# Adafruit_NeoPixel_Ring_60_Quarter_rev_B.net
KiCad netlist of a schematic drawn in EAGLE
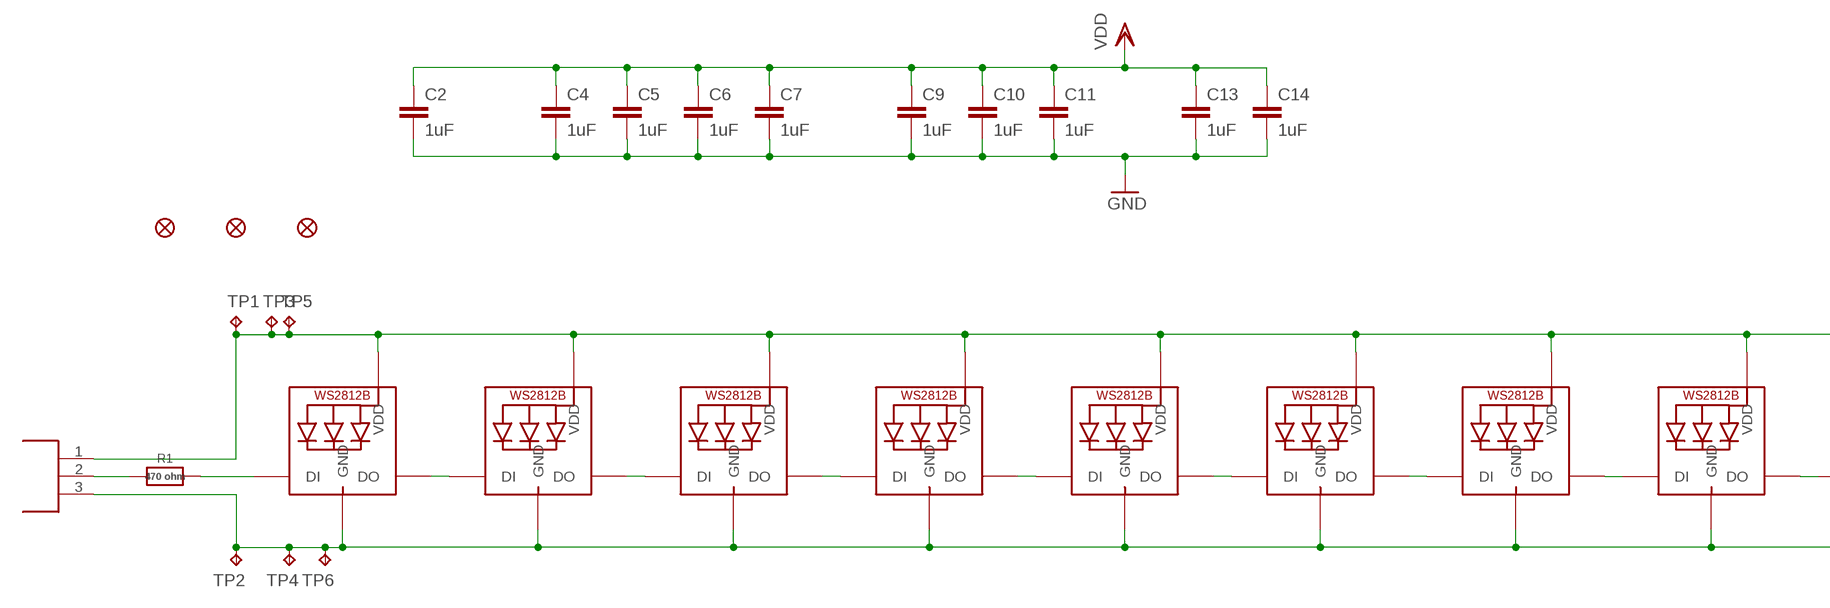
[diagram p0: schematic, sheet 1, part 1 of 2]
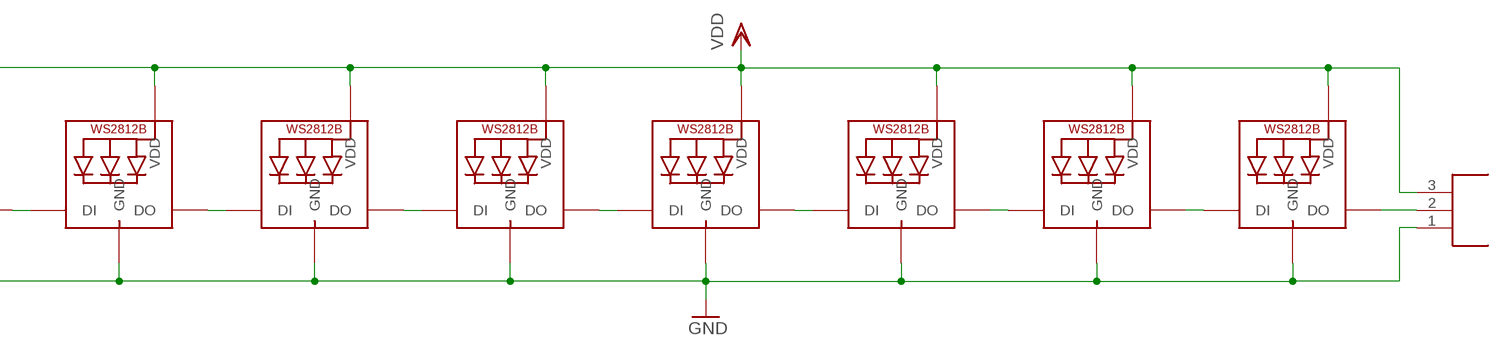
[diagram p1: schematic, sheet 1, part 2 of 2]

(export (version "E")
  (design (tool "Eeschema 10.0.6"))
  (components
    (comp (ref "C2")
      (value "1uF")
      (footprint "eagle-import:C0603")
      (libsource (lib "eagle-import") (part "C-EUC0603"))
    )
    (comp (ref "C4")
      (value "1uF")
      (footprint "eagle-import:C0603")
      (libsource (lib "eagle-import") (part "C-EUC0603"))
    )
    (comp (ref "C5")
      (value "1uF")
      (footprint "eagle-import:C0603")
      (libsource (lib "eagle-import") (part "C-EUC0603"))
    )
    (comp (ref "C6")
      (value "1uF")
      (footprint "eagle-import:C0603")
      (libsource (lib "eagle-import") (part "C-EUC0603"))
    )
    (comp (ref "C7")
      (value "1uF")
      (footprint "eagle-import:C0603")
      (libsource (lib "eagle-import") (part "C-EUC0603"))
    )
    (comp (ref "C9")
      (value "1uF")
      (footprint "eagle-import:C0603")
      (libsource (lib "eagle-import") (part "C-EUC0603"))
    )
    (comp (ref "C10")
      (value "1uF")
      (footprint "eagle-import:C0603")
      (libsource (lib "eagle-import") (part "C-EUC0603"))
    )
    (comp (ref "C11")
      (value "1uF")
      (footprint "eagle-import:C0603")
      (libsource (lib "eagle-import") (part "C-EUC0603"))
    )
    (comp (ref "C13")
      (value "1uF")
      (footprint "eagle-import:C0603")
      (libsource (lib "eagle-import") (part "C-EUC0603"))
    )
    (comp (ref "C14")
      (value "1uF")
      (footprint "eagle-import:C0603")
      (libsource (lib "eagle-import") (part "C-EUC0603"))
    )
    (comp (ref "FID1")
      (value "FIDUCIAL_1MM")
      (footprint "eagle-import:FIDUCIAL_1MM")
      (libsource (lib "eagle-import") (part "FIDUCIAL_1MM"))
    )
    (comp (ref "FID2")
      (value "FIDUCIAL_1MM")
      (footprint "eagle-import:FIDUCIAL_1MM")
      (libsource (lib "eagle-import") (part "FIDUCIAL_1MM"))
    )
    (comp (ref "FID3")
      (value "FIDUCIAL_1MM")
      (footprint "eagle-import:FIDUCIAL_1MM")
      (libsource (lib "eagle-import") (part "FIDUCIAL_1MM"))
    )
    (comp (ref "LED1")
      (value "WS2812B_5050N")
      (footprint "eagle-import:WS2812B-NARROW")
      (libsource (lib "eagle-import") (part "WS2812B_5050N"))
    )
    (comp (ref "LED2")
      (value "WS2812B_5050N")
      (footprint "eagle-import:WS2812B-NARROW")
      (libsource (lib "eagle-import") (part "WS2812B_5050N"))
    )
    (comp (ref "LED3")
      (value "WS2812B_5050N")
      (footprint "eagle-import:WS2812B-NARROW")
      (libsource (lib "eagle-import") (part "WS2812B_5050N"))
    )
    (comp (ref "LED4")
      (value "WS2812B_5050N")
      (footprint "eagle-import:WS2812B-NARROW")
      (libsource (lib "eagle-import") (part "WS2812B_5050N"))
    )
    (comp (ref "LED5")
      (value "WS2812B_5050N")
      (footprint "eagle-import:WS2812B-NARROW")
      (libsource (lib "eagle-import") (part "WS2812B_5050N"))
    )
    (comp (ref "LED6")
      (value "WS2812B_5050N")
      (footprint "eagle-import:WS2812B-NARROW")
      (libsource (lib "eagle-import") (part "WS2812B_5050N"))
    )
    (comp (ref "LED7")
      (value "WS2812B_5050N")
      (footprint "eagle-import:WS2812B-NARROW")
      (libsource (lib "eagle-import") (part "WS2812B_5050N"))
    )
    (comp (ref "LED8")
      (value "WS2812B_5050N")
      (footprint "eagle-import:WS2812B-NARROW")
      (libsource (lib "eagle-import") (part "WS2812B_5050N"))
    )
    (comp (ref "LED9")
      (value "WS2812B_5050N")
      (footprint "eagle-import:WS2812B-NARROW")
      (libsource (lib "eagle-import") (part "WS2812B_5050N"))
    )
    (comp (ref "LED10")
      (value "WS2812B_5050N")
      (footprint "eagle-import:WS2812B-NARROW")
      (libsource (lib "eagle-import") (part "WS2812B_5050N"))
    )
    (comp (ref "LED11")
      (value "WS2812B_5050N")
      (footprint "eagle-import:WS2812B-NARROW")
      (libsource (lib "eagle-import") (part "WS2812B_5050N"))
    )
    (comp (ref "LED12")
      (value "WS2812B_5050N")
      (footprint "eagle-import:WS2812B-NARROW")
      (libsource (lib "eagle-import") (part "WS2812B_5050N"))
    )
    (comp (ref "LED13")
      (value "WS2812B_5050N")
      (footprint "eagle-import:WS2812B-NARROW")
      (libsource (lib "eagle-import") (part "WS2812B_5050N"))
    )
    (comp (ref "LED14")
      (value "WS2812B_5050N")
      (footprint "eagle-import:WS2812B-NARROW")
      (libsource (lib "eagle-import") (part "WS2812B_5050N"))
    )
    (comp (ref "LED15")
      (value "WS2812B_5050N")
      (footprint "eagle-import:WS2812B-NARROW")
      (libsource (lib "eagle-import") (part "WS2812B_5050N"))
    )
    (comp (ref "R1")
      (value "470 ohm")
      (footprint "eagle-import:0603-NO")
      (libsource (lib "eagle-import") (part "RESISTOR_0603_NOOUT"))
    )
    (comp (ref "TP1")
      (value "TPTP20R")
      (footprint "eagle-import:TP20R")
      (libsource (lib "eagle-import") (part "TPTP20R"))
    )
    (comp (ref "TP2")
      (value "TPTP20R")
      (footprint "eagle-import:TP20R")
      (libsource (lib "eagle-import") (part "TPTP20R"))
    )
    (comp (ref "TP3")
      (value "TPTP20R")
      (footprint "eagle-import:TP20R")
      (libsource (lib "eagle-import") (part "TPTP20R"))
    )
    (comp (ref "TP4")
      (value "TPTP20R")
      (footprint "eagle-import:TP20R")
      (libsource (lib "eagle-import") (part "TPTP20R"))
    )
    (comp (ref "TP5")
      (value "TPTP20R")
      (footprint "eagle-import:TP20R")
      (libsource (lib "eagle-import") (part "TPTP20R"))
    )
    (comp (ref "TP6")
      (value "TPTP20R")
      (footprint "eagle-import:TP20R")
      (libsource (lib "eagle-import") (part "TPTP20R"))
    )
    (comp (ref "U$1")
      (value "DNP")
      (footprint "eagle-import:RING_END_CONN_X3")
      (libsource (lib "eagle-import") (part "RING_END_CONN_X3"))
    )
    (comp (ref "U$2")
      (value "DNP")
      (footprint "eagle-import:RING_END_CONN_X3")
      (libsource (lib "eagle-import") (part "RING_END_CONN_X3"))
    )
  )
  (nets
    (net (code "1") (name "GND") (class "Default")
      (node (ref "C10") (pin "2") (pinfunction "2_2") (pintype "passive"))
      (node (ref "C11") (pin "2") (pinfunction "2_2") (pintype "passive"))
      (node (ref "C13") (pin "2") (pinfunction "2_2") (pintype "passive"))
      (node (ref "C14") (pin "2") (pinfunction "2_2") (pintype "passive"))
      (node (ref "C2") (pin "2") (pinfunction "2_2") (pintype "passive"))
      (node (ref "C4") (pin "2") (pinfunction "2_2") (pintype "passive"))
      (node (ref "C5") (pin "2") (pinfunction "2_2") (pintype "passive"))
      (node (ref "C6") (pin "2") (pinfunction "2_2") (pintype "passive"))
      (node (ref "C7") (pin "2") (pinfunction "2_2") (pintype "passive"))
      (node (ref "C9") (pin "2") (pinfunction "2_2") (pintype "passive"))
      (node (ref "LED1") (pin "3-GND") (pinfunction "GND_3-GND") (pintype "power_in"))
      (node (ref "LED10") (pin "3-GND") (pinfunction "GND_3-GND") (pintype "power_in"))
      (node (ref "LED11") (pin "3-GND") (pinfunction "GND_3-GND") (pintype "power_in"))
      (node (ref "LED12") (pin "3-GND") (pinfunction "GND_3-GND") (pintype "power_in"))
      (node (ref "LED13") (pin "3-GND") (pinfunction "GND_3-GND") (pintype "power_in"))
      (node (ref "LED14") (pin "3-GND") (pinfunction "GND_3-GND") (pintype "power_in"))
      (node (ref "LED15") (pin "3-GND") (pinfunction "GND_3-GND") (pintype "power_in"))
      (node (ref "LED2") (pin "3-GND") (pinfunction "GND_3-GND") (pintype "power_in"))
      (node (ref "LED3") (pin "3-GND") (pinfunction "GND_3-GND") (pintype "power_in"))
      (node (ref "LED4") (pin "3-GND") (pinfunction "GND_3-GND") (pintype "power_in"))
      (node (ref "LED5") (pin "3-GND") (pinfunction "GND_3-GND") (pintype "power_in"))
      (node (ref "LED6") (pin "3-GND") (pinfunction "GND_3-GND") (pintype "power_in"))
      (node (ref "LED7") (pin "3-GND") (pinfunction "GND_3-GND") (pintype "power_in"))
      (node (ref "LED8") (pin "3-GND") (pinfunction "GND_3-GND") (pintype "power_in"))
      (node (ref "LED9") (pin "3-GND") (pinfunction "GND_3-GND") (pintype "power_in"))
      (node (ref "TP2") (pin "TP") (pinfunction "TP_TP") (pintype "input"))
      (node (ref "TP4") (pin "TP") (pinfunction "TP_TP") (pintype "input"))
      (node (ref "TP6") (pin "TP") (pinfunction "TP_TP") (pintype "input"))
      (node (ref "U$1") (pin "3") (pinfunction "P$3_3") (pintype "bidirectional"))
      (node (ref "U$2") (pin "1") (pinfunction "P$1_1") (pintype "bidirectional"))
    )
    (net (code "2") (name "Net-(LED1-DI)") (class "Default")
      (node (ref "LED1") (pin "4-DIN") (pinfunction "DI_4-DIN") (pintype "input"))
      (node (ref "R1") (pin "2") (pinfunction "2_2") (pintype "passive"))
    )
    (net (code "3") (name "Net-(LED1-DO)") (class "Default")
      (node (ref "LED1") (pin "2-DOUT") (pinfunction "DO_2-DOUT") (pintype "output"))
      (node (ref "LED2") (pin "4-DIN") (pinfunction "DI_4-DIN") (pintype "input"))
    )
    (net (code "4") (name "Net-(LED2-DO)") (class "Default")
      (node (ref "LED2") (pin "2-DOUT") (pinfunction "DO_2-DOUT") (pintype "output"))
      (node (ref "LED3") (pin "4-DIN") (pinfunction "DI_4-DIN") (pintype "input"))
    )
    (net (code "5") (name "Net-(LED3-DO)") (class "Default")
      (node (ref "LED3") (pin "2-DOUT") (pinfunction "DO_2-DOUT") (pintype "output"))
      (node (ref "LED4") (pin "4-DIN") (pinfunction "DI_4-DIN") (pintype "input"))
    )
    (net (code "6") (name "Net-(LED4-DO)") (class "Default")
      (node (ref "LED4") (pin "2-DOUT") (pinfunction "DO_2-DOUT") (pintype "output"))
      (node (ref "LED5") (pin "4-DIN") (pinfunction "DI_4-DIN") (pintype "input"))
    )
    (net (code "7") (name "Net-(LED5-DO)") (class "Default")
      (node (ref "LED5") (pin "2-DOUT") (pinfunction "DO_2-DOUT") (pintype "output"))
      (node (ref "LED6") (pin "4-DIN") (pinfunction "DI_4-DIN") (pintype "input"))
    )
    (net (code "8") (name "Net-(LED6-DO)") (class "Default")
      (node (ref "LED6") (pin "2-DOUT") (pinfunction "DO_2-DOUT") (pintype "output"))
      (node (ref "LED7") (pin "4-DIN") (pinfunction "DI_4-DIN") (pintype "input"))
    )
    (net (code "9") (name "Net-(LED7-DO)") (class "Default")
      (node (ref "LED7") (pin "2-DOUT") (pinfunction "DO_2-DOUT") (pintype "output"))
      (node (ref "LED8") (pin "4-DIN") (pinfunction "DI_4-DIN") (pintype "input"))
    )
    (net (code "10") (name "Net-(LED8-DO)") (class "Default")
      (node (ref "LED8") (pin "2-DOUT") (pinfunction "DO_2-DOUT") (pintype "output"))
      (node (ref "LED9") (pin "4-DIN") (pinfunction "DI_4-DIN") (pintype "input"))
    )
    (net (code "11") (name "Net-(LED10-DI)") (class "Default")
      (node (ref "LED10") (pin "4-DIN") (pinfunction "DI_4-DIN") (pintype "input"))
      (node (ref "LED9") (pin "2-DOUT") (pinfunction "DO_2-DOUT") (pintype "output"))
    )
    (net (code "12") (name "Net-(LED10-DO)") (class "Default")
      (node (ref "LED10") (pin "2-DOUT") (pinfunction "DO_2-DOUT") (pintype "output"))
      (node (ref "LED11") (pin "4-DIN") (pinfunction "DI_4-DIN") (pintype "input"))
    )
    (net (code "13") (name "Net-(LED11-DO)") (class "Default")
      (node (ref "LED11") (pin "2-DOUT") (pinfunction "DO_2-DOUT") (pintype "output"))
      (node (ref "LED12") (pin "4-DIN") (pinfunction "DI_4-DIN") (pintype "input"))
    )
    (net (code "14") (name "Net-(LED12-DO)") (class "Default")
      (node (ref "LED12") (pin "2-DOUT") (pinfunction "DO_2-DOUT") (pintype "output"))
      (node (ref "LED13") (pin "4-DIN") (pinfunction "DI_4-DIN") (pintype "input"))
    )
    (net (code "15") (name "Net-(LED13-DO)") (class "Default")
      (node (ref "LED13") (pin "2-DOUT") (pinfunction "DO_2-DOUT") (pintype "output"))
      (node (ref "LED14") (pin "4-DIN") (pinfunction "DI_4-DIN") (pintype "input"))
    )
    (net (code "16") (name "Net-(LED14-DO)") (class "Default")
      (node (ref "LED14") (pin "2-DOUT") (pinfunction "DO_2-DOUT") (pintype "output"))
      (node (ref "LED15") (pin "4-DIN") (pinfunction "DI_4-DIN") (pintype "input"))
    )
    (net (code "17") (name "Net-(LED15-DO)") (class "Default")
      (node (ref "LED15") (pin "2-DOUT") (pinfunction "DO_2-DOUT") (pintype "output"))
      (node (ref "U$2") (pin "2") (pinfunction "P$2_2") (pintype "bidirectional"))
    )
    (net (code "18") (name "Net-(U$1-P$2)") (class "Default")
      (node (ref "R1") (pin "1") (pinfunction "1_1") (pintype "passive"))
      (node (ref "U$1") (pin "2") (pinfunction "P$2_2") (pintype "bidirectional"))
    )
    (net (code "19") (name "VDD") (class "Default")
      (node (ref "C10") (pin "1") (pinfunction "1_1") (pintype "passive"))
      (node (ref "C11") (pin "1") (pinfunction "1_1") (pintype "passive"))
      (node (ref "C13") (pin "1") (pinfunction "1_1") (pintype "passive"))
      (node (ref "C14") (pin "1") (pinfunction "1_1") (pintype "passive"))
      (node (ref "C2") (pin "1") (pinfunction "1_1") (pintype "passive"))
      (node (ref "C4") (pin "1") (pinfunction "1_1") (pintype "passive"))
      (node (ref "C5") (pin "1") (pinfunction "1_1") (pintype "passive"))
      (node (ref "C6") (pin "1") (pinfunction "1_1") (pintype "passive"))
      (node (ref "C7") (pin "1") (pinfunction "1_1") (pintype "passive"))
      (node (ref "C9") (pin "1") (pinfunction "1_1") (pintype "passive"))
      (node (ref "LED1") (pin "1-VDD") (pinfunction "VDD_1-VDD") (pintype "power_in"))
      (node (ref "LED10") (pin "1-VDD") (pinfunction "VDD_1-VDD") (pintype "power_in"))
      (node (ref "LED11") (pin "1-VDD") (pinfunction "VDD_1-VDD") (pintype "power_in"))
      (node (ref "LED12") (pin "1-VDD") (pinfunction "VDD_1-VDD") (pintype "power_in"))
      (node (ref "LED13") (pin "1-VDD") (pinfunction "VDD_1-VDD") (pintype "power_in"))
      (node (ref "LED14") (pin "1-VDD") (pinfunction "VDD_1-VDD") (pintype "power_in"))
      (node (ref "LED15") (pin "1-VDD") (pinfunction "VDD_1-VDD") (pintype "power_in"))
      (node (ref "LED2") (pin "1-VDD") (pinfunction "VDD_1-VDD") (pintype "power_in"))
      (node (ref "LED3") (pin "1-VDD") (pinfunction "VDD_1-VDD") (pintype "power_in"))
      (node (ref "LED4") (pin "1-VDD") (pinfunction "VDD_1-VDD") (pintype "power_in"))
      (node (ref "LED5") (pin "1-VDD") (pinfunction "VDD_1-VDD") (pintype "power_in"))
      (node (ref "LED6") (pin "1-VDD") (pinfunction "VDD_1-VDD") (pintype "power_in"))
      (node (ref "LED7") (pin "1-VDD") (pinfunction "VDD_1-VDD") (pintype "power_in"))
      (node (ref "LED8") (pin "1-VDD") (pinfunction "VDD_1-VDD") (pintype "power_in"))
      (node (ref "LED9") (pin "1-VDD") (pinfunction "VDD_1-VDD") (pintype "power_in"))
      (node (ref "TP1") (pin "TP") (pinfunction "TP_TP") (pintype "input"))
      (node (ref "TP3") (pin "TP") (pinfunction "TP_TP") (pintype "input"))
      (node (ref "TP5") (pin "TP") (pinfunction "TP_TP") (pintype "input"))
      (node (ref "U$1") (pin "1") (pinfunction "P$1_1") (pintype "bidirectional"))
      (node (ref "U$2") (pin "3") (pinfunction "P$3_3") (pintype "bidirectional"))
    )
  )
)
